# X-Bus.net
KiCad netlist of a schematic drawn in Altium Designer
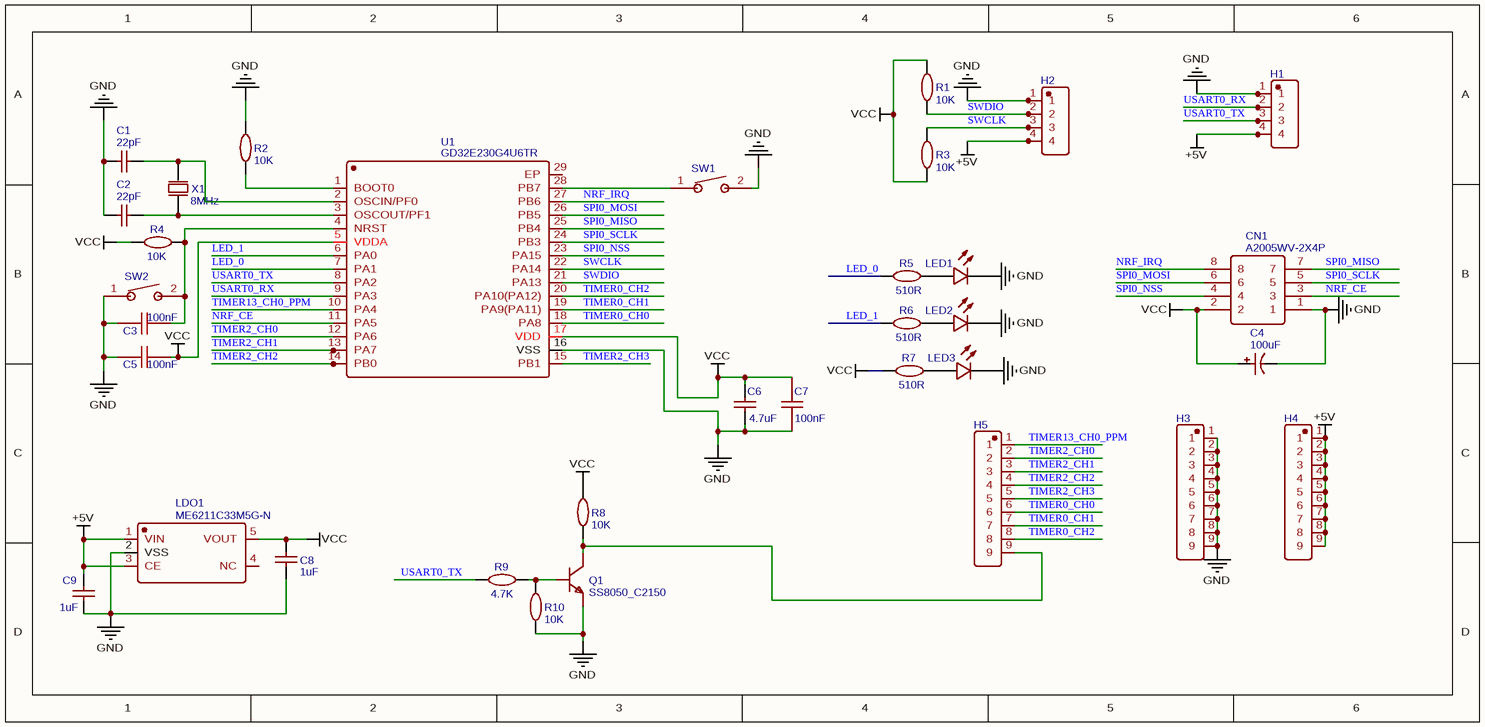
[diagram p0: X-Bus.schdoc]

(export (version "E")
  (design (tool "Eeschema 10.0.6"))
  (components
    (comp (ref "C1")
      (value "22pF")
      (footprint "C0603_L")
      (fields
        (field (name "BOM_MANUFACTURER PART") "CC0603JRNPO9BN220")
        (field (name "BOM_SUPPLIER PART") "C105620")
      )
      (libsource (lib "altium-import") (part "root_0_22pF_"))
    )
    (comp (ref "C2")
      (value "22pF")
      (footprint "C0603_L")
      (fields
        (field (name "BOM_MANUFACTURER PART") "CC0603JRNPO9BN220")
        (field (name "BOM_SUPPLIER PART") "C105620")
      )
      (libsource (lib "altium-import") (part "root_0_22pF_"))
    )
    (comp (ref "C3")
      (value "100nF")
      (footprint "C0603_L")
      (fields
        (field (name "BOM_MANUFACTURER PART") "CC0603KRX7R9BB104")
        (field (name "BOM_SUPPLIER PART") "C14663")
      )
      (libsource (lib "altium-import") (part "root_2_100nF_"))
    )
    (comp (ref "C4")
      (value "100uF")
      (footprint "CAP 2.5*6.3*11.2-H - BK")
      (fields
        (field (name "BOM_MANUFACTURER PART") "35YXJ100M6.3X11")
        (field (name "BOM_SUPPLIER PART") "C88754")
      )
      (libsource (lib "altium-import") (part "root_0_100uF_"))
    )
    (comp (ref "C5")
      (value "100nF")
      (footprint "C0603_L")
      (fields
        (field (name "BOM_MANUFACTURER PART") "CC0603KRX7R9BB104")
        (field (name "BOM_SUPPLIER PART") "C14663")
      )
      (libsource (lib "altium-import") (part "root_0_100nF_"))
    )
    (comp (ref "C6")
      (value "4.7uF")
      (footprint "C0603_L")
      (fields
        (field (name "BOM_MANUFACTURER PART") "CL10A475KO8NNNC")
        (field (name "BOM_SUPPLIER PART") "C19666")
      )
      (libsource (lib "altium-import") (part "root_3_4.7uF_"))
    )
    (comp (ref "C7")
      (value "100nF")
      (footprint "C0603_L")
      (fields
        (field (name "BOM_MANUFACTURER PART") "CC0603KRX7R9BB104")
        (field (name "BOM_SUPPLIER PART") "C14663")
      )
      (libsource (lib "altium-import") (part "root_3_100nF_"))
    )
    (comp (ref "C8")
      (value "1uF")
      (footprint "C0603_L")
      (fields
        (field (name "BOM_MANUFACTURER PART") "CL10A105KB8NNNC")
        (field (name "BOM_SUPPLIER PART") "C15849")
      )
      (libsource (lib "altium-import") (part "root_1_1uF_"))
    )
    (comp (ref "C9")
      (value "1uF")
      (footprint "C0603_L")
      (fields
        (field (name "BOM_MANUFACTURER PART") "CL10A105KB8NNNC")
        (field (name "BOM_SUPPLIER PART") "C15849")
      )
      (libsource (lib "altium-import") (part "root_1_1uF_"))
    )
    (comp (ref "CN1")
      (value "A2005WV-2X4P")
      (footprint "NRF24L01_E01")
      (fields
        (field (name "BOM_SUPPLIER PART") "C225289")
        (field (name "BOM_MANUFACTURER PART") "A2005WV-2x4P")
        (field (name "CONTRIBUTOR") "LCSC")
      )
      (libsource (lib "altium-import") (part "root_1_A2005WV-2X4P_"))
    )
    (comp (ref "H1")
      (value "GP26-2520WV-4P")
      (footprint "HDR2.54-LI-4P")
      (fields (field (name "BOM_SUPPLIER PART") "C2681739") (field (name "CONTRIBUTOR") "LCSC"))
      (libsource (lib "altium-import") (part "root_0_GP26-2520WV-4P_"))
    )
    (comp (ref "H2")
      (value "GP26-2520WV-4P")
      (footprint "HDR2.54-LI-4P")
      (fields (field (name "BOM_SUPPLIER PART") "C2681739") (field (name "CONTRIBUTOR") "LCSC"))
      (libsource (lib "altium-import") (part "root_0_GP26-2520WV-4P_"))
    )
    (comp (ref "H3")
      (value "PZ254V-11-09P")
      (footprint "HDR2.54-LI-9P")
      (fields (field (name "BOM_SUPPLIER PART") "C492408") (field (name "CONTRIBUTOR") "LCSC"))
      (libsource (lib "altium-import") (part "root_0_PZ254V-11-09P_"))
    )
    (comp (ref "H4")
      (value "PZ254V-11-09P")
      (footprint "HDR2.54-LI-9P")
      (fields (field (name "BOM_SUPPLIER PART") "C492408") (field (name "CONTRIBUTOR") "LCSC"))
      (libsource (lib "altium-import") (part "root_0_PZ254V-11-09P_"))
    )
    (comp (ref "H5")
      (value "PZ254V-11-09P")
      (footprint "HDR2.54-LI-9P")
      (fields (field (name "BOM_SUPPLIER PART") "C492408") (field (name "CONTRIBUTOR") "LCSC"))
      (libsource (lib "altium-import") (part "root_0_PZ254V-11-09P_"))
    )
    (comp (ref "LDO1")
      (value "ME6211C33M5G-N")
      (footprint "ME6211")
      (fields (field (name "BOM_SUPPLIER PART") "C82942"))
      (libsource (lib "altium-import") (part "root_0_ME6211C33M5G-N_"))
    )
    (comp (ref "LED1")
      (value "19-217/GHC-YR1S2/3T")
      (footprint "LED 3MM-B")
      (fields (field (name "BOM_SUPPLIER PART") "C72043"))
      (libsource (lib "altium-import") (part "root_0_19-217/GHC-YR1S2/3T_"))
    )
    (comp (ref "LED2")
      (value "19-217/GHC-YR1S2/3T")
      (footprint "LED 3MM-G")
      (fields (field (name "BOM_SUPPLIER PART") "C72043"))
      (libsource (lib "altium-import") (part "root_0_19-217/GHC-YR1S2/3T_"))
    )
    (comp (ref "LED3")
      (value "19-217/GHC-YR1S2/3T")
      (footprint "LED 3MM-R")
      (fields (field (name "BOM_SUPPLIER PART") "C72043"))
      (libsource (lib "altium-import") (part "root_0_19-217/GHC-YR1S2/3T_"))
    )
    (comp (ref "Q1")
      (value "SS8050_C2150")
      (footprint "SS8050")
      (fields (field (name "BOM_MANUFACTURER PART") "SS8050") (field (name "BOM_SUPPLIER PART") "C2150"))
      (libsource (lib "altium-import") (part "root_0_SS8050_C2150_"))
    )
    (comp (ref "R1")
      (value "10K")
      (footprint "R0603_L")
      (fields
        (field (name "BOM_MANUFACTURER PART") "RC0603FR-0710KL")
        (field (name "BOM_SUPPLIER PART") "C98220")
      )
      (libsource (lib "altium-import") (part "root_1_10K_"))
    )
    (comp (ref "R2")
      (value "10K")
      (footprint "R0603_L")
      (fields
        (field (name "BOM_MANUFACTURER PART") "RC0603FR-0710KL")
        (field (name "BOM_SUPPLIER PART") "C98220")
      )
      (libsource (lib "altium-import") (part "root_1_10K_"))
    )
    (comp (ref "R3")
      (value "10K")
      (footprint "R0603_L")
      (fields
        (field (name "BOM_MANUFACTURER PART") "RC0603FR-0710KL")
        (field (name "BOM_SUPPLIER PART") "C98220")
      )
      (libsource (lib "altium-import") (part "root_1_10K_"))
    )
    (comp (ref "R4")
      (value "10K")
      (footprint "R0603_L")
      (fields
        (field (name "BOM_MANUFACTURER PART") "RC0603FR-0710KL")
        (field (name "BOM_SUPPLIER PART") "C98220")
      )
      (libsource (lib "altium-import") (part "root_2_10K_"))
    )
    (comp (ref "R5")
      (value "510R")
      (footprint "R0603_L")
      (fields
        (field (name "BOM_MANUFACTURER PART") "RC0603FR-0710KL")
        (field (name "BOM_SUPPLIER PART") "C98220")
      )
      (libsource (lib "altium-import") (part "root_2_510R_"))
    )
    (comp (ref "R6")
      (value "510R")
      (footprint "R0603_L")
      (fields
        (field (name "BOM_MANUFACTURER PART") "RC0603FR-0710KL")
        (field (name "BOM_SUPPLIER PART") "C98220")
      )
      (libsource (lib "altium-import") (part "root_2_510R_"))
    )
    (comp (ref "R7")
      (value "510R")
      (footprint "R0603_L")
      (fields
        (field (name "BOM_MANUFACTURER PART") "RC0603FR-0710KL")
        (field (name "BOM_SUPPLIER PART") "C98220")
      )
      (libsource (lib "altium-import") (part "root_2_510R_"))
    )
    (comp (ref "R8")
      (value "10K")
      (footprint "R0603_L")
      (fields
        (field (name "BOM_MANUFACTURER PART") "RC0603FR-0710KL")
        (field (name "BOM_SUPPLIER PART") "C98220")
      )
      (libsource (lib "altium-import") (part "root_1_10K_"))
    )
    (comp (ref "R9")
      (value "4.7K")
      (footprint "R0603_L")
      (fields
        (field (name "BOM_MANUFACTURER PART") "RC0603FR-0710KL")
        (field (name "BOM_SUPPLIER PART") "C98220")
      )
      (libsource (lib "altium-import") (part "root_2_4.7K_"))
    )
    (comp (ref "R10")
      (value "10K")
      (footprint "R0603_L")
      (fields
        (field (name "BOM_MANUFACTURER PART") "RC0603FR-0710KL")
        (field (name "BOM_SUPPLIER PART") "C98220")
      )
      (libsource (lib "altium-import") (part "root_1_10K_"))
    )
    (comp (ref "SW1")
      (value "TSA363G25-250B")
      (footprint "YD-3410")
      (fields (field (name "BOM_SUPPLIER PART") "C354943") (field (name "CONTRIBUTOR") "LCSC"))
      (libsource (lib "altium-import") (part "root_0_TSA363G25-250B_"))
    )
    (comp (ref "SW2")
      (value "TSA363G25-250B")
      (footprint "YD-3410")
      (fields (field (name "BOM_SUPPLIER PART") "C354943") (field (name "CONTRIBUTOR") "LCSC"))
      (libsource (lib "altium-import") (part "root_0_TSA363G25-250B_"))
    )
    (comp (ref "U1")
      (value "GD32E230G4U6TR")
      (footprint "QFN-28_L4.0-W4.0-P0.40-BL-EP")
      (fields (field (name "BOM_SUPPLIER PART") "C380784") (field (name "CONTRIBUTOR") "LCSC"))
      (libsource (lib "altium-import") (part "root_0_GD32E230G4U6TR_"))
    )
    (comp (ref "X1")
      (value "8MHz")
      (footprint "OSC 5032-8M")
      (fields (field (name "BOM_SUPPLIER PART") "C122522") (field (name "CONTRIBUTOR") "LCSC"))
      (libsource (lib "altium-import") (part "root_1_8MHz_"))
    )
  )
  (nets
    (net (code "1") (name "+5V") (class "Default")
      (node (ref "C9") (pin "2") (pinfunction "2_2") (pintype "passive"))
      (node (ref "H1") (pin "4") (pinfunction "4_4") (pintype "passive"))
      (node (ref "H2") (pin "4") (pinfunction "4_4") (pintype "passive"))
      (node (ref "H4") (pin "1") (pinfunction "1_1") (pintype "passive"))
      (node (ref "H4") (pin "2") (pinfunction "2_2") (pintype "passive"))
      (node (ref "H4") (pin "3") (pinfunction "3_3") (pintype "passive"))
      (node (ref "H4") (pin "4") (pinfunction "4_4") (pintype "passive"))
      (node (ref "H4") (pin "5") (pinfunction "5_5") (pintype "passive"))
      (node (ref "H4") (pin "6") (pinfunction "6_6") (pintype "passive"))
      (node (ref "H4") (pin "7") (pinfunction "7_7") (pintype "passive"))
      (node (ref "H4") (pin "8") (pinfunction "8_8") (pintype "passive"))
      (node (ref "H4") (pin "9") (pinfunction "9_9") (pintype "passive"))
      (node (ref "LDO1") (pin "1") (pinfunction "VIN_1") (pintype "passive"))
      (node (ref "LDO1") (pin "3") (pinfunction "CE_3") (pintype "passive"))
    )
    (net (code "2") (name "/LED_0") (class "Default")
      (node (ref "R5") (pin "2") (pinfunction "2_2") (pintype "passive"))
      (node (ref "U1") (pin "7") (pinfunction "PA1_7") (pintype "passive"))
    )
    (net (code "3") (name "/LED_1") (class "Default")
      (node (ref "R6") (pin "2") (pinfunction "2_2") (pintype "passive"))
      (node (ref "U1") (pin "6") (pinfunction "PA0_6") (pintype "passive"))
    )
    (net (code "4") (name "/NRF_CE") (class "Default")
      (node (ref "CN1") (pin "3") (pinfunction "3_3") (pintype "passive"))
      (node (ref "U1") (pin "11") (pinfunction "PA5_11") (pintype "passive"))
    )
    (net (code "5") (name "/NRF_IRQ") (class "Default")
      (node (ref "CN1") (pin "8") (pinfunction "8_8") (pintype "passive"))
      (node (ref "U1") (pin "27") (pinfunction "PB6_27") (pintype "passive"))
    )
    (net (code "6") (name "/SPI0_MISO") (class "Default")
      (node (ref "CN1") (pin "7") (pinfunction "7_7") (pintype "passive"))
      (node (ref "U1") (pin "25") (pinfunction "PB4_25") (pintype "passive"))
    )
    (net (code "7") (name "/SPI0_MOSI") (class "Default")
      (node (ref "CN1") (pin "6") (pinfunction "6_6") (pintype "passive"))
      (node (ref "U1") (pin "26") (pinfunction "PB5_26") (pintype "passive"))
    )
    (net (code "8") (name "/SPI0_NSS") (class "Default")
      (node (ref "CN1") (pin "4") (pinfunction "4_4") (pintype "passive"))
      (node (ref "U1") (pin "23") (pinfunction "PA15_23") (pintype "passive"))
    )
    (net (code "9") (name "/SPI0_SCLK") (class "Default")
      (node (ref "CN1") (pin "5") (pinfunction "5_5") (pintype "passive"))
      (node (ref "U1") (pin "24") (pinfunction "PB3_24") (pintype "passive"))
    )
    (net (code "10") (name "/SWCLK") (class "Default")
      (node (ref "H2") (pin "3") (pinfunction "3_3") (pintype "passive"))
      (node (ref "R3") (pin "2") (pinfunction "2_2") (pintype "passive"))
      (node (ref "U1") (pin "22") (pinfunction "PA14_22") (pintype "passive"))
    )
    (net (code "11") (name "/SWDIO") (class "Default")
      (node (ref "H2") (pin "2") (pinfunction "2_2") (pintype "passive"))
      (node (ref "R1") (pin "1") (pinfunction "1_1") (pintype "passive"))
      (node (ref "U1") (pin "21") (pinfunction "PA13_21") (pintype "passive"))
    )
    (net (code "12") (name "/TIMER0_CH0") (class "Default")
      (node (ref "H5") (pin "6") (pinfunction "6_6") (pintype "passive"))
      (node (ref "U1") (pin "18") (pinfunction "PA8_18") (pintype "passive"))
    )
    (net (code "13") (name "/TIMER0_CH1") (class "Default")
      (node (ref "H5") (pin "7") (pinfunction "7_7") (pintype "passive"))
      (node (ref "U1") (pin "19") (pinfunction "PA9(PA11)_19") (pintype "passive"))
    )
    (net (code "14") (name "/TIMER0_CH2") (class "Default")
      (node (ref "H5") (pin "8") (pinfunction "8_8") (pintype "passive"))
      (node (ref "U1") (pin "20") (pinfunction "PA10(PA12)_20") (pintype "passive"))
    )
    (net (code "15") (name "/TIMER2_CH0") (class "Default")
      (node (ref "H5") (pin "2") (pinfunction "2_2") (pintype "passive"))
      (node (ref "U1") (pin "12") (pinfunction "PA6_12") (pintype "passive"))
    )
    (net (code "16") (name "/TIMER2_CH1") (class "Default")
      (node (ref "H5") (pin "3") (pinfunction "3_3") (pintype "passive"))
      (node (ref "U1") (pin "13") (pinfunction "PA7_13") (pintype "passive"))
    )
    (net (code "17") (name "/TIMER2_CH2") (class "Default")
      (node (ref "H5") (pin "4") (pinfunction "4_4") (pintype "passive"))
      (node (ref "U1") (pin "14") (pinfunction "PB0_14") (pintype "passive"))
    )
    (net (code "18") (name "/TIMER2_CH3") (class "Default")
      (node (ref "H5") (pin "5") (pinfunction "5_5") (pintype "passive"))
      (node (ref "U1") (pin "15") (pinfunction "PB1_15") (pintype "passive"))
    )
    (net (code "19") (name "/TIMER13_CH0_PPM") (class "Default")
      (node (ref "H5") (pin "1") (pinfunction "1_1") (pintype "passive"))
      (node (ref "U1") (pin "10") (pinfunction "PA4_10") (pintype "passive"))
    )
    (net (code "20") (name "/USART0_RX") (class "Default")
      (node (ref "H1") (pin "2") (pinfunction "2_2") (pintype "passive"))
      (node (ref "U1") (pin "9") (pinfunction "PA3_9") (pintype "passive"))
    )
    (net (code "21") (name "/USART0_TX") (class "Default")
      (node (ref "H1") (pin "3") (pinfunction "3_3") (pintype "passive"))
      (node (ref "R9") (pin "2") (pinfunction "2_2") (pintype "passive"))
      (node (ref "U1") (pin "8") (pinfunction "PA2_8") (pintype "passive"))
    )
    (net (code "22") (name "GND") (class "Default")
      (node (ref "C1") (pin "1") (pinfunction "1_1") (pintype "passive"))
      (node (ref "C2") (pin "1") (pinfunction "1_1") (pintype "passive"))
      (node (ref "C3") (pin "2") (pinfunction "2_2") (pintype "passive"))
      (node (ref "C4") (pin "2") (pinfunction "2_2") (pintype "passive"))
      (node (ref "C5") (pin "1") (pinfunction "1_1") (pintype "passive"))
      (node (ref "C6") (pin "2") (pinfunction "2_2") (pintype "passive"))
      (node (ref "C7") (pin "2") (pinfunction "2_2") (pintype "passive"))
      (node (ref "C8") (pin "1") (pinfunction "1_1") (pintype "passive"))
      (node (ref "C9") (pin "1") (pinfunction "1_1") (pintype "passive"))
      (node (ref "CN1") (pin "1") (pinfunction "1_1") (pintype "passive"))
      (node (ref "H1") (pin "1") (pinfunction "1_1") (pintype "passive"))
      (node (ref "H2") (pin "1") (pinfunction "1_1") (pintype "passive"))
      (node (ref "H3") (pin "1") (pinfunction "1_1") (pintype "passive"))
      (node (ref "H3") (pin "2") (pinfunction "2_2") (pintype "passive"))
      (node (ref "H3") (pin "3") (pinfunction "3_3") (pintype "passive"))
      (node (ref "H3") (pin "4") (pinfunction "4_4") (pintype "passive"))
      (node (ref "H3") (pin "5") (pinfunction "5_5") (pintype "passive"))
      (node (ref "H3") (pin "6") (pinfunction "6_6") (pintype "passive"))
      (node (ref "H3") (pin "7") (pinfunction "7_7") (pintype "passive"))
      (node (ref "H3") (pin "8") (pinfunction "8_8") (pintype "passive"))
      (node (ref "H3") (pin "9") (pinfunction "9_9") (pintype "passive"))
      (node (ref "LDO1") (pin "2") (pinfunction "VSS_2") (pintype "passive"))
      (node (ref "LED1") (pin "2") (pinfunction "C_2") (pintype "passive"))
      (node (ref "LED2") (pin "2") (pinfunction "C_2") (pintype "passive"))
      (node (ref "LED3") (pin "2") (pinfunction "C_2") (pintype "passive"))
      (node (ref "Q1") (pin "2") (pinfunction "E_2") (pintype "passive"))
      (node (ref "R10") (pin "1") (pinfunction "1_1") (pintype "passive"))
      (node (ref "R2") (pin "2") (pinfunction "2_2") (pintype "passive"))
      (node (ref "SW1") (pin "2") (pinfunction "2_2") (pintype "passive"))
      (node (ref "SW2") (pin "1") (pinfunction "1_1") (pintype "passive"))
      (node (ref "U1") (pin "16") (pinfunction "VSS_16") (pintype "passive"))
    )
    (net (code "23") (name "Net-(LED1-A)") (class "Default")
      (node (ref "LED1") (pin "1") (pinfunction "A_1") (pintype "passive"))
      (node (ref "R5") (pin "1") (pinfunction "1_1") (pintype "passive"))
    )
    (net (code "24") (name "Net-(LED2-A)") (class "Default")
      (node (ref "LED2") (pin "1") (pinfunction "A_1") (pintype "passive"))
      (node (ref "R6") (pin "1") (pinfunction "1_1") (pintype "passive"))
    )
    (net (code "25") (name "Net-(LED3-A)") (class "Default")
      (node (ref "LED3") (pin "1") (pinfunction "A_1") (pintype "passive"))
      (node (ref "R7") (pin "1") (pinfunction "1_1") (pintype "passive"))
    )
    (net (code "26") (name "Net-(Q1-B)") (class "Default")
      (node (ref "Q1") (pin "1") (pinfunction "B_1") (pintype "passive"))
      (node (ref "R10") (pin "2") (pinfunction "2_2") (pintype "passive"))
      (node (ref "R9") (pin "1") (pinfunction "1_1") (pintype "passive"))
    )
    (net (code "27") (name "Net-(Q1-C)") (class "Default")
      (node (ref "H5") (pin "9") (pinfunction "9_9") (pintype "passive"))
      (node (ref "Q1") (pin "3") (pinfunction "C_3") (pintype "passive"))
      (node (ref "R8") (pin "1") (pinfunction "1_1") (pintype "passive"))
    )
    (net (code "28") (name "Net-(U1-BOOT0)") (class "Default")
      (node (ref "R2") (pin "1") (pinfunction "1_1") (pintype "passive"))
      (node (ref "U1") (pin "1") (pinfunction "BOOT0_1") (pintype "passive"))
    )
    (net (code "29") (name "Net-(U1-NRST)") (class "Default")
      (node (ref "C3") (pin "1") (pinfunction "1_1") (pintype "passive"))
      (node (ref "R4") (pin "1") (pinfunction "1_1") (pintype "passive"))
      (node (ref "SW2") (pin "2") (pinfunction "2_2") (pintype "passive"))
      (node (ref "U1") (pin "4") (pinfunction "NRST_4") (pintype "passive"))
    )
    (net (code "30") (name "Net-(U1-OSCIN{slash}PF0)") (class "Default")
      (node (ref "C1") (pin "2") (pinfunction "2_2") (pintype "passive"))
      (node (ref "U1") (pin "2") (pinfunction "OSCIN/PF0_2") (pintype "passive"))
      (node (ref "X1") (pin "2") (pinfunction "OSC2_2") (pintype "passive"))
    )
    (net (code "31") (name "Net-(U1-OSCOUT{slash}PF1)") (class "Default")
      (node (ref "C2") (pin "2") (pinfunction "2_2") (pintype "passive"))
      (node (ref "U1") (pin "3") (pinfunction "OSCOUT/PF1_3") (pintype "passive"))
      (node (ref "X1") (pin "1") (pinfunction "OSC1_1") (pintype "passive"))
    )
    (net (code "32") (name "Net-(U1-PB7)") (class "Default")
      (node (ref "SW1") (pin "1") (pinfunction "1_1") (pintype "passive"))
      (node (ref "U1") (pin "28") (pinfunction "PB7_28") (pintype "passive"))
    )
    (net (code "33") (name "VCC") (class "Default")
      (node (ref "C4") (pin "1") (pinfunction "1_1") (pintype "passive"))
      (node (ref "C5") (pin "2") (pinfunction "2_2") (pintype "passive"))
      (node (ref "C6") (pin "1") (pinfunction "1_1") (pintype "passive"))
      (node (ref "C7") (pin "1") (pinfunction "1_1") (pintype "passive"))
      (node (ref "C8") (pin "2") (pinfunction "2_2") (pintype "passive"))
      (node (ref "CN1") (pin "2") (pinfunction "2_2") (pintype "passive"))
      (node (ref "LDO1") (pin "5") (pinfunction "VOUT_5") (pintype "passive"))
      (node (ref "R1") (pin "2") (pinfunction "2_2") (pintype "passive"))
      (node (ref "R3") (pin "1") (pinfunction "1_1") (pintype "passive"))
      (node (ref "R4") (pin "2") (pinfunction "2_2") (pintype "passive"))
      (node (ref "R7") (pin "2") (pinfunction "2_2") (pintype "passive"))
      (node (ref "R8") (pin "2") (pinfunction "2_2") (pintype "passive"))
      (node (ref "U1") (pin "17") (pinfunction "VDD_17") (pintype "passive"))
      (node (ref "U1") (pin "5") (pinfunction "VDDA_5") (pintype "passive"))
    )
    (net (code "34") (name "unconnected-(LDO1-NC-Pad4)") (class "Default")
      (node (ref "LDO1") (pin "4") (pinfunction "NC_4") (pintype "passive"))
    )
    (net (code "35") (name "unconnected-(U1-EP-Pad29)") (class "Default")
      (node (ref "U1") (pin "29") (pinfunction "EP_29") (pintype "passive"))
    )
  )
)
